# STM32_PCB.net
KiCad netlist of a schematic drawn in Altium Designer
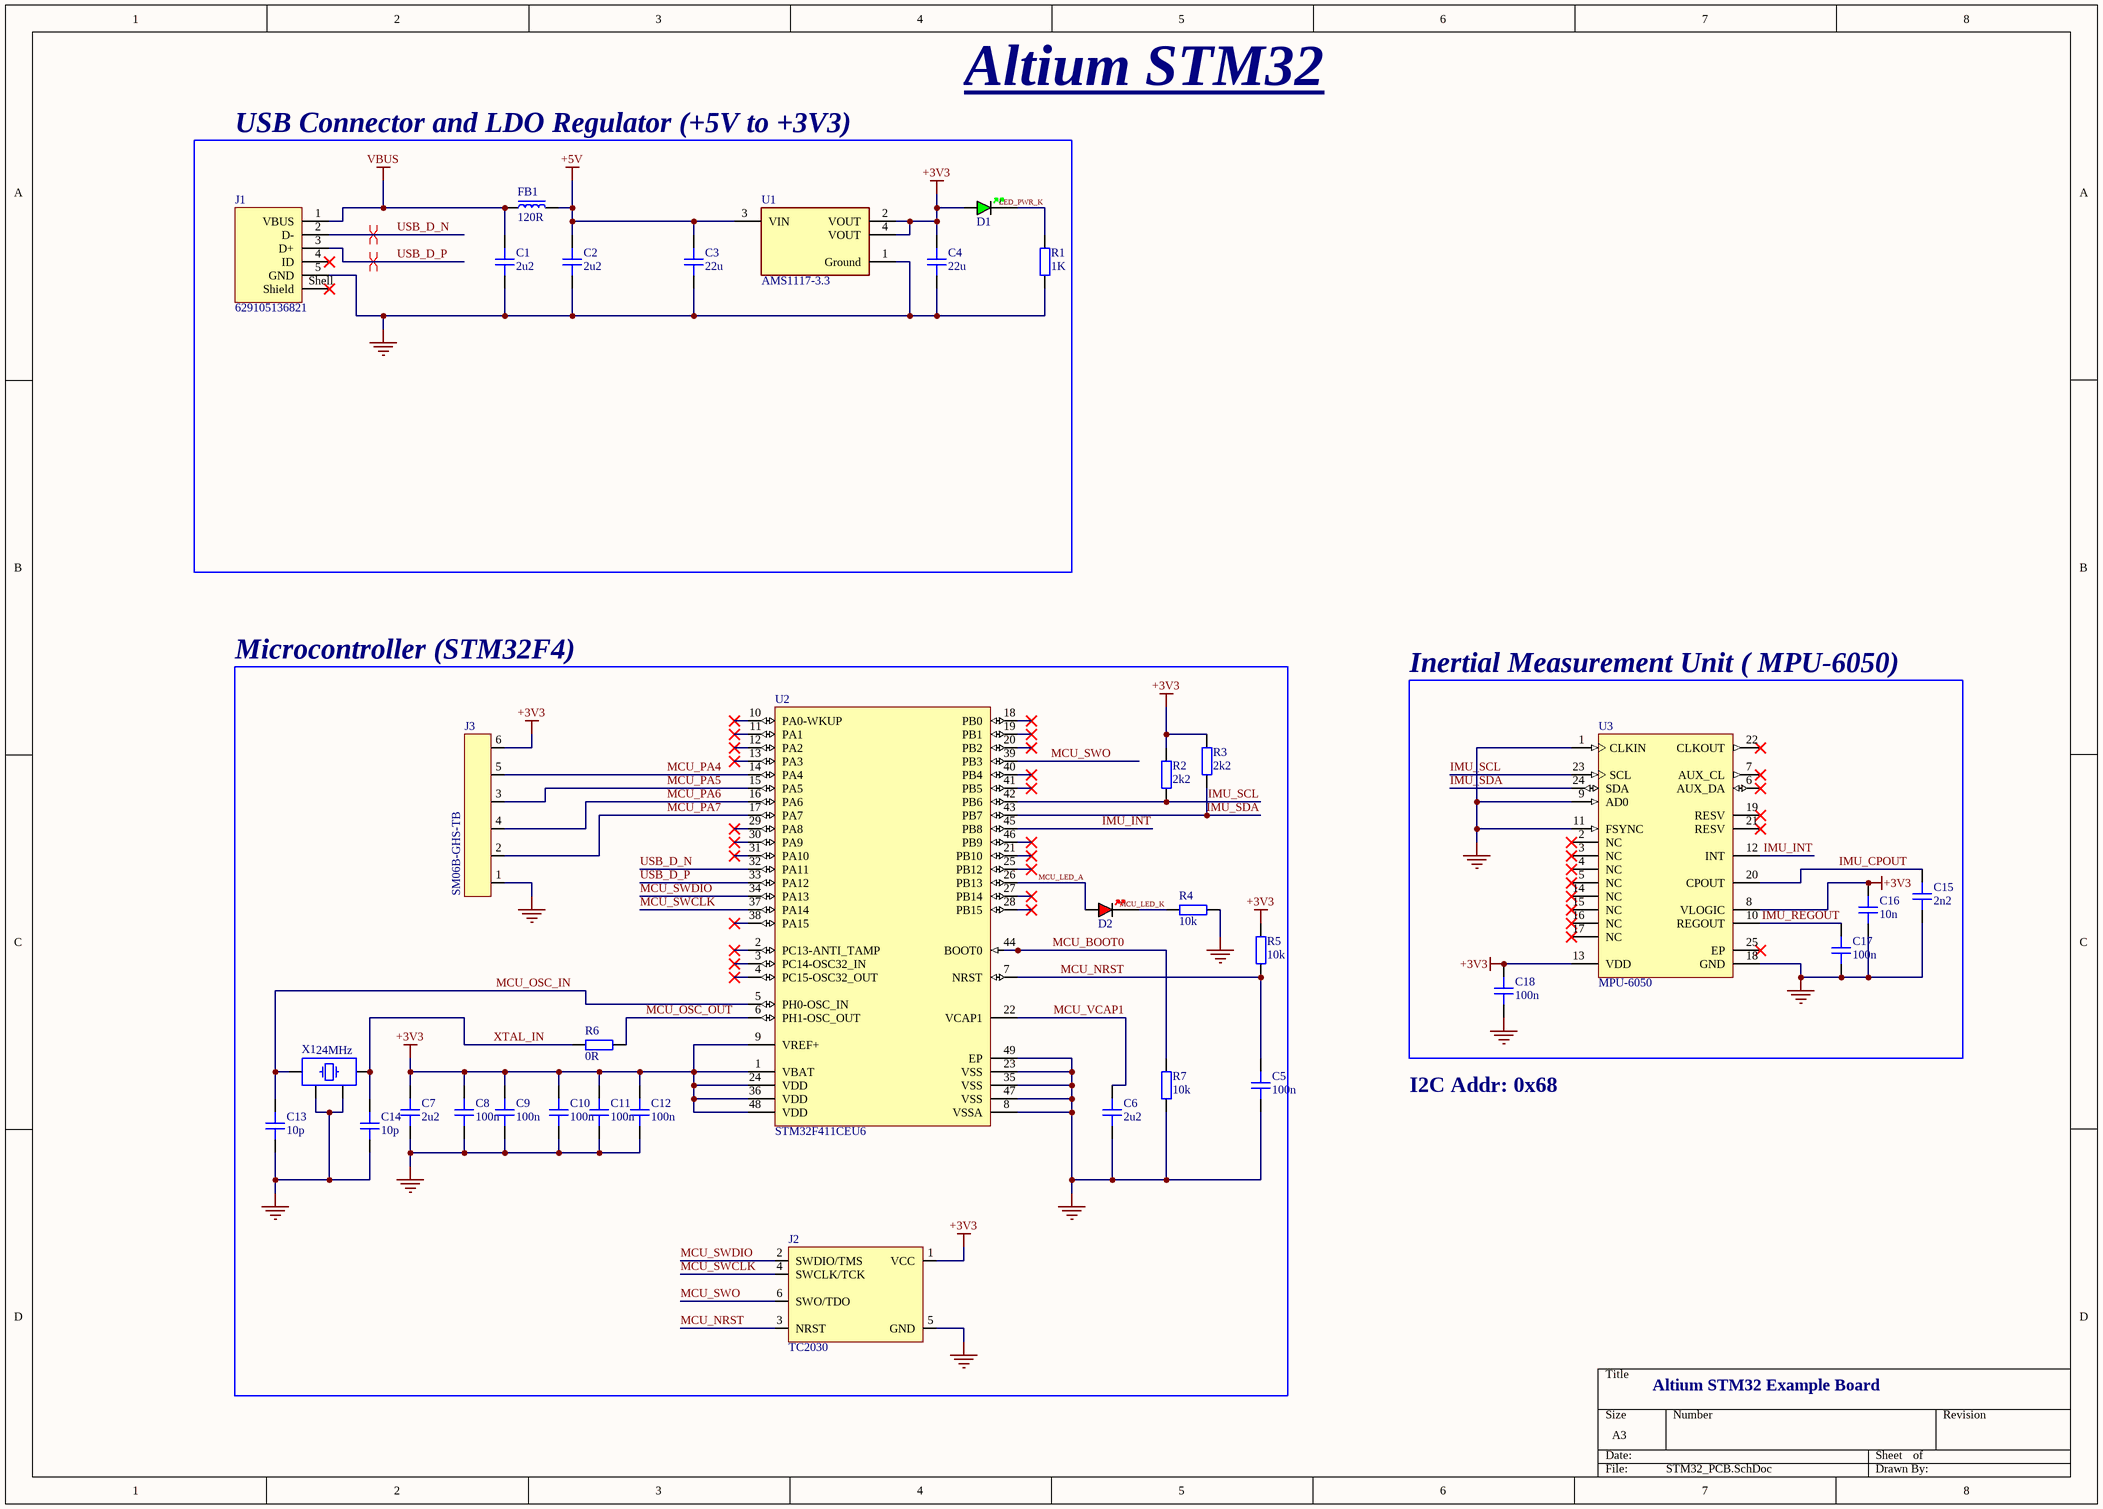
[diagram p0: STM32_PCB.SchDoc]

(export (version "E")
  (design (tool "Eeschema 10.0.6"))
  (components
    (comp (ref "C1")
      (value "2u2")
      (footprint "CAP_0603")
      (description "Capacitor SMD 0603 16V")
      (libsource (lib "Schematic-Lib-PhilsLab") (part "CAP_0603"))
    )
    (comp (ref "C2")
      (value "2u2")
      (footprint "CAP_0603")
      (description "Capacitor SMD 0603 16V")
      (libsource (lib "Schematic-Lib-PhilsLab") (part "CAP_0603"))
    )
    (comp (ref "C3")
      (value "22u")
      (footprint "CAP_0805")
      (description "Capacitor SMD 0805 16V")
      (libsource (lib "Schematic-Lib-PhilsLab") (part "CAP_0805"))
    )
    (comp (ref "C4")
      (value "22u")
      (footprint "CAP_0805")
      (description "Capacitor SMD 0805 16V")
      (libsource (lib "Schematic-Lib-PhilsLab") (part "CAP_0805"))
    )
    (comp (ref "C5")
      (value "100n")
      (footprint "CAP_0402")
      (description "Capacitor SMD 0402 16V")
      (libsource (lib "Schematic-Lib-PhilsLab") (part "CAP_0402"))
    )
    (comp (ref "C6")
      (value "2u2")
      (footprint "CAP_0603")
      (description "Capacitor SMD 0603 16V")
      (libsource (lib "Schematic-Lib-PhilsLab") (part "CAP_0603"))
    )
    (comp (ref "C7")
      (value "2u2")
      (footprint "CAP_0603")
      (description "Capacitor SMD 0603 16V")
      (libsource (lib "Schematic-Lib-PhilsLab") (part "CAP_0603"))
    )
    (comp (ref "C8")
      (value "100n")
      (footprint "CAP_0402")
      (description "Capacitor SMD 0402 16V")
      (libsource (lib "Schematic-Lib-PhilsLab") (part "CAP_0402"))
    )
    (comp (ref "C9")
      (value "100n")
      (footprint "CAP_0402")
      (description "Capacitor SMD 0402 16V")
      (libsource (lib "Schematic-Lib-PhilsLab") (part "CAP_0402"))
    )
    (comp (ref "C10")
      (value "100n")
      (footprint "CAP_0402")
      (description "Capacitor SMD 0402 16V")
      (libsource (lib "Schematic-Lib-PhilsLab") (part "CAP_0402"))
    )
    (comp (ref "C11")
      (value "100n")
      (footprint "CAP_0402")
      (description "Capacitor SMD 0402 16V")
      (libsource (lib "Schematic-Lib-PhilsLab") (part "CAP_0402"))
    )
    (comp (ref "C12")
      (value "100n")
      (footprint "CAP_0402")
      (description "Capacitor SMD 0402 16V")
      (libsource (lib "Schematic-Lib-PhilsLab") (part "CAP_0402"))
    )
    (comp (ref "C13")
      (value "10p")
      (footprint "CAP_0402")
      (description "Capacitor SMD 0402 16V")
      (libsource (lib "Schematic-Lib-PhilsLab") (part "CAP_0402"))
    )
    (comp (ref "C14")
      (value "10p")
      (footprint "CAP_0402")
      (description "Capacitor SMD 0402 16V")
      (libsource (lib "Schematic-Lib-PhilsLab") (part "CAP_0402"))
    )
    (comp (ref "C15")
      (value "2n2")
      (footprint "CAP_0402")
      (description "Capacitor SMD 0402 16V")
      (libsource (lib "Schematic-Lib-PhilsLab") (part "CAP_0402"))
    )
    (comp (ref "C16")
      (value "10n")
      (footprint "CAP_0402")
      (description "Capacitor SMD 0402 16V")
      (libsource (lib "Schematic-Lib-PhilsLab") (part "CAP_0402"))
    )
    (comp (ref "C17")
      (value "100n")
      (footprint "CAP_0402")
      (description "Capacitor SMD 0402 16V")
      (libsource (lib "Schematic-Lib-PhilsLab") (part "CAP_0402"))
    )
    (comp (ref "C18")
      (value "100n")
      (footprint "CAP_0402")
      (description "Capacitor SMD 0402 16V")
      (libsource (lib "Schematic-Lib-PhilsLab") (part "CAP_0402"))
    )
    (comp (ref "D1")
      (value "GREEN")
      (footprint "LED_0402_GREEN")
      (description "LED 0402 GREEN SMD")
      (libsource (lib "Schematic-Lib-PhilsLab") (part "LED_0402_GREEN"))
    )
    (comp (ref "D2")
      (value "RED")
      (footprint "LED_0402_RED")
      (description "LED 0402 RED SMD")
      (libsource (lib "Schematic-Lib-PhilsLab") (part "LED_0402_RED"))
    )
    (comp (ref "FB1")
      (value "120R")
      (footprint "FB_0603")
      (description "Ferrite Bead SMD 0603")
      (libsource (lib "Schematic-Lib-PhilsLab") (part "FB_0603"))
    )
    (comp (ref "J1")
      (value "629105136821")
      (footprint "629105136821")
      (libsource (lib "Altium Content Vault") (part "Micro USB 2.0_Type B_Receptacle_1 Port"))
    )
    (comp (ref "J2")
      (value "TC2030")
      (footprint "TC2030-FP")
      (description "Tag-Connect No-Solder SWD Debug Connector DO NOT PLACE")
      (fields (field (name "MANUFACTURER") "Tag-Connect"))
      (libsource (lib "Schematic-Lib-PhilsLab") (part "TC2030"))
    )
    (comp (ref "J3")
      (value "SM06B-GHS-TB")
      (footprint "SM06B-GHS-TB")
      (description "Header Connector 6 Position 1.25MM Pitch SMD Horizontal JST GH")
      (fields (field (name "MANUFACTURER") "JST"))
      (libsource (lib "Schematic-Lib-PhilsLab") (part "SM06B-GHS-TB"))
    )
    (comp (ref "R1")
      (value "1K")
      (footprint "RES_0402")
      (description "Resistor SMD 0402")
      (libsource (lib "Schematic-Lib-PhilsLab") (part "RES_0402"))
    )
    (comp (ref "R2")
      (value "2k2")
      (footprint "RES_0402")
      (description "Resistor SMD 0402")
      (libsource (lib "Schematic-Lib-PhilsLab") (part "RES_0402"))
    )
    (comp (ref "R3")
      (value "2k2")
      (footprint "RES_0402")
      (description "Resistor SMD 0402")
      (libsource (lib "Schematic-Lib-PhilsLab") (part "RES_0402"))
    )
    (comp (ref "R4")
      (value "10k")
      (footprint "RES_0402")
      (description "Resistor SMD 0402")
      (libsource (lib "Schematic-Lib-PhilsLab") (part "RES_0402"))
    )
    (comp (ref "R5")
      (value "10k")
      (footprint "RES_0402")
      (description "Resistor SMD 0402")
      (libsource (lib "Schematic-Lib-PhilsLab") (part "RES_0402"))
    )
    (comp (ref "R6")
      (value "0R")
      (footprint "RES_0402")
      (description "Resistor SMD 0402")
      (libsource (lib "Schematic-Lib-PhilsLab") (part "RES_0402"))
    )
    (comp (ref "R7")
      (value "10k")
      (footprint "RES_0402")
      (description "Resistor SMD 0402")
      (libsource (lib "Schematic-Lib-PhilsLab") (part "RES_0402"))
    )
    (comp (ref "U1")
      (value "AMS1117-3.3")
      (footprint "FP-AMS1117-IPC_C")
      (description "LDO Voltage Regulators 1A, 3.3V")
      (fields
        (field (name "OCTOPART") "https://octopart.com/ams1117-3.3-advanced+monolithic+systems-25899300")
        (field (name "MANUFACTURER") "Advanced Monolithic Systems")
      )
      (libsource (lib "Altium Content Vault") (part "8bdbb5f8e77002000e30dd2845d0354"))
    )
    (comp (ref "U2")
      (value "STM32F411CEU6")
      (footprint "STM-UFQFPN48_L")
      (libsource (lib "Altium Content Vault") (part "MC-ARM-STM32F411-UFQFPN48"))
    )
    (comp (ref "U3")
      (value "MPU-6050")
      (footprint "IS-QFN-24_V")
      (fields (field (name "MANUFACTURER") "InvenSense"))
      (libsource (lib "Altium Content Vault") (part "IS-MPU-6050-QFN-24"))
    )
    (comp (ref "X1")
      (value "24MHz")
      (footprint "XTAL_3225")
      (description "Crystal SMD 24MHz 10PPM 7pF 3225")
      (fields
        (field (name "MANUFACTURER") "Epson")
        (field (name "MANUFACTURER PART NUMBER") "TSX-3225 24.0000MF15X-AC")
      )
      (libsource (lib "Schematic-Lib-PhilsLab") (part "TSX-3225_24.0000MF15X-AC"))
    )
  )
  (nets
    (net (code "1") (name "+3V3") (class "Default")
      (node (ref "C10") (pin "2") (pinfunction "2_2") (pintype "passive"))
      (node (ref "C11") (pin "2") (pinfunction "2_2") (pintype "passive"))
      (node (ref "C12") (pin "2") (pinfunction "2_2") (pintype "passive"))
      (node (ref "C16") (pin "2") (pinfunction "2_2") (pintype "passive"))
      (node (ref "C18") (pin "2") (pinfunction "2_2") (pintype "passive"))
      (node (ref "C4") (pin "2") (pinfunction "2_2") (pintype "passive"))
      (node (ref "C7") (pin "2") (pinfunction "2_2") (pintype "passive"))
      (node (ref "C8") (pin "2") (pinfunction "2_2") (pintype "passive"))
      (node (ref "C9") (pin "2") (pinfunction "2_2") (pintype "passive"))
      (node (ref "D1") (pin "A") (pinfunction "A_A") (pintype "passive"))
      (node (ref "J2") (pin "1") (pinfunction "VCC_1") (pintype "passive"))
      (node (ref "J3") (pin "6") (pinfunction "6_6") (pintype "passive"))
      (node (ref "R2") (pin "2") (pinfunction "2_2") (pintype "passive"))
      (node (ref "R3") (pin "2") (pinfunction "2_2") (pintype "passive"))
      (node (ref "R5") (pin "2") (pinfunction "2_2") (pintype "passive"))
      (node (ref "U1") (pin "2") (pinfunction "VOUT_2") (pintype "passive"))
      (node (ref "U1") (pin "4") (pinfunction "VOUT_4") (pintype "passive"))
      (node (ref "U2") (pin "1") (pinfunction "VBAT_1") (pintype "power_in"))
      (node (ref "U2") (pin "24") (pinfunction "VDD_24") (pintype "power_in"))
      (node (ref "U2") (pin "36") (pinfunction "VDD_36") (pintype "power_in"))
      (node (ref "U2") (pin "48") (pinfunction "VDD_48") (pintype "power_in"))
      (node (ref "U2") (pin "9") (pinfunction "VREF+_9") (pintype "power_in"))
      (node (ref "U3") (pin "13") (pinfunction "VDD_13") (pintype "power_in"))
      (node (ref "U3") (pin "8") (pinfunction "VLOGIC_8") (pintype "power_in"))
    )
    (net (code "2") (name "+5V") (class "Default")
      (node (ref "C2") (pin "2") (pinfunction "2_2") (pintype "passive"))
      (node (ref "C3") (pin "2") (pinfunction "2_2") (pintype "passive"))
      (node (ref "FB1") (pin "2") (pinfunction "2_2") (pintype "passive"))
      (node (ref "U1") (pin "3") (pinfunction "VIN_3") (pintype "power_in"))
    )
    (net (code "3") (name "/IMU_CPOUT") (class "Default")
      (node (ref "C15") (pin "2") (pinfunction "2_2") (pintype "passive"))
      (node (ref "U3") (pin "20") (pinfunction "CPOUT_20") (pintype "passive"))
    )
    (net (code "4") (name "/IMU_INT") (class "Default")
      (node (ref "U2") (pin "45") (pinfunction "PB8_45") (pintype "bidirectional"))
      (node (ref "U3") (pin "12") (pinfunction "INT_12") (pintype "open_collector"))
    )
    (net (code "5") (name "/IMU_REGOUT") (class "Default")
      (node (ref "C17") (pin "2") (pinfunction "2_2") (pintype "passive"))
      (node (ref "U3") (pin "10") (pinfunction "REGOUT_10") (pintype "passive"))
    )
    (net (code "6") (name "/IMU_SCL") (class "Default")
      (node (ref "R2") (pin "1") (pinfunction "1_1") (pintype "passive"))
      (node (ref "U2") (pin "42") (pinfunction "PB6_42") (pintype "bidirectional"))
      (node (ref "U3") (pin "23") (pinfunction "SCL_23") (pintype "input"))
    )
    (net (code "7") (name "/IMU_SDA") (class "Default")
      (node (ref "R3") (pin "1") (pinfunction "1_1") (pintype "passive"))
      (node (ref "U2") (pin "43") (pinfunction "PB7_43") (pintype "bidirectional"))
      (node (ref "U3") (pin "24") (pinfunction "SDA_24") (pintype "bidirectional"))
    )
    (net (code "8") (name "/LED_PWR_K") (class "Default")
      (node (ref "D1") (pin "K") (pinfunction "K_K") (pintype "passive"))
      (node (ref "R1") (pin "2") (pinfunction "2_2") (pintype "passive"))
    )
    (net (code "9") (name "/MCU_BOOT0") (class "Default")
      (node (ref "R7") (pin "2") (pinfunction "2_2") (pintype "passive"))
      (node (ref "U2") (pin "44") (pinfunction "BOOT0_44") (pintype "input"))
    )
    (net (code "10") (name "/MCU_LED_A") (class "Default")
      (node (ref "D2") (pin "A") (pinfunction "A_A") (pintype "passive"))
      (node (ref "U2") (pin "26") (pinfunction "PB13_26") (pintype "bidirectional"))
    )
    (net (code "11") (name "/MCU_LED_K") (class "Default")
      (node (ref "D2") (pin "K") (pinfunction "K_K") (pintype "passive"))
      (node (ref "R4") (pin "2") (pinfunction "2_2") (pintype "passive"))
    )
    (net (code "12") (name "/MCU_NRST") (class "Default")
      (node (ref "C5") (pin "2") (pinfunction "2_2") (pintype "passive"))
      (node (ref "J2") (pin "3") (pinfunction "NRST_3") (pintype "passive"))
      (node (ref "R5") (pin "1") (pinfunction "1_1") (pintype "passive"))
      (node (ref "U2") (pin "7") (pinfunction "NRST_7") (pintype "bidirectional"))
    )
    (net (code "13") (name "/MCU_OSC_IN") (class "Default")
      (node (ref "C13") (pin "2") (pinfunction "2_2") (pintype "passive"))
      (node (ref "U2") (pin "5") (pinfunction "PH0-OSC_IN_5") (pintype "bidirectional"))
      (node (ref "X1") (pin "1") (pinfunction "1_1") (pintype "passive"))
    )
    (net (code "14") (name "/MCU_OSC_OUT") (class "Default")
      (node (ref "R6") (pin "1") (pinfunction "1_1") (pintype "passive"))
      (node (ref "U2") (pin "6") (pinfunction "PH1-OSC_OUT_6") (pintype "bidirectional"))
    )
    (net (code "15") (name "/MCU_PA4") (class "Default")
      (node (ref "J3") (pin "5") (pinfunction "5_5") (pintype "passive"))
      (node (ref "U2") (pin "14") (pinfunction "PA4_14") (pintype "bidirectional"))
    )
    (net (code "16") (name "/MCU_PA5") (class "Default")
      (node (ref "J3") (pin "3") (pinfunction "3_3") (pintype "passive"))
      (node (ref "U2") (pin "15") (pinfunction "PA5_15") (pintype "bidirectional"))
    )
    (net (code "17") (name "/MCU_PA6") (class "Default")
      (node (ref "J3") (pin "4") (pinfunction "4_4") (pintype "passive"))
      (node (ref "U2") (pin "16") (pinfunction "PA6_16") (pintype "bidirectional"))
    )
    (net (code "18") (name "/MCU_PA7") (class "Default")
      (node (ref "J3") (pin "2") (pinfunction "2_2") (pintype "passive"))
      (node (ref "U2") (pin "17") (pinfunction "PA7_17") (pintype "bidirectional"))
    )
    (net (code "19") (name "/MCU_SWCLK") (class "Default")
      (node (ref "J2") (pin "4") (pinfunction "SWCLK/TCK_4") (pintype "passive"))
      (node (ref "U2") (pin "37") (pinfunction "PA14_37") (pintype "bidirectional"))
    )
    (net (code "20") (name "/MCU_SWDIO") (class "Default")
      (node (ref "J2") (pin "2") (pinfunction "SWDIO/TMS_2") (pintype "passive"))
      (node (ref "U2") (pin "34") (pinfunction "PA13_34") (pintype "bidirectional"))
    )
    (net (code "21") (name "/MCU_SWO") (class "Default")
      (node (ref "J2") (pin "6") (pinfunction "SWO/TDO_6") (pintype "passive"))
      (node (ref "U2") (pin "39") (pinfunction "PB3_39") (pintype "bidirectional"))
    )
    (net (code "22") (name "/MCU_VCAP1") (class "Default")
      (node (ref "C6") (pin "2") (pinfunction "2_2") (pintype "passive"))
      (node (ref "U2") (pin "22") (pinfunction "VCAP1_22") (pintype "passive"))
    )
    (net (code "23") (name "/USB_D_N") (class "Default")
      (node (ref "J1") (pin "2") (pinfunction "D-_2") (pintype "passive"))
      (node (ref "U2") (pin "32") (pinfunction "PA11_32") (pintype "bidirectional"))
    )
    (net (code "24") (name "/USB_D_P") (class "Default")
      (node (ref "J1") (pin "3") (pinfunction "D+_3") (pintype "passive"))
      (node (ref "U2") (pin "33") (pinfunction "PA12_33") (pintype "bidirectional"))
    )
    (net (code "25") (name "/XTAL_IN") (class "Default")
      (node (ref "C14") (pin "2") (pinfunction "2_2") (pintype "passive"))
      (node (ref "R6") (pin "2") (pinfunction "2_2") (pintype "passive"))
      (node (ref "X1") (pin "3") (pinfunction "3_3") (pintype "passive"))
    )
    (net (code "26") (name "GND") (class "Default")
      (node (ref "C1") (pin "1") (pinfunction "1_1") (pintype "passive"))
      (node (ref "C10") (pin "1") (pinfunction "1_1") (pintype "passive"))
      (node (ref "C11") (pin "1") (pinfunction "1_1") (pintype "passive"))
      (node (ref "C12") (pin "1") (pinfunction "1_1") (pintype "passive"))
      (node (ref "C13") (pin "1") (pinfunction "1_1") (pintype "passive"))
      (node (ref "C14") (pin "1") (pinfunction "1_1") (pintype "passive"))
      (node (ref "C15") (pin "1") (pinfunction "1_1") (pintype "passive"))
      (node (ref "C16") (pin "1") (pinfunction "1_1") (pintype "passive"))
      (node (ref "C17") (pin "1") (pinfunction "1_1") (pintype "passive"))
      (node (ref "C18") (pin "1") (pinfunction "1_1") (pintype "passive"))
      (node (ref "C2") (pin "1") (pinfunction "1_1") (pintype "passive"))
      (node (ref "C3") (pin "1") (pinfunction "1_1") (pintype "passive"))
      (node (ref "C4") (pin "1") (pinfunction "1_1") (pintype "passive"))
      (node (ref "C5") (pin "1") (pinfunction "1_1") (pintype "passive"))
      (node (ref "C6") (pin "1") (pinfunction "1_1") (pintype "passive"))
      (node (ref "C7") (pin "1") (pinfunction "1_1") (pintype "passive"))
      (node (ref "C8") (pin "1") (pinfunction "1_1") (pintype "passive"))
      (node (ref "C9") (pin "1") (pinfunction "1_1") (pintype "passive"))
      (node (ref "J1") (pin "5") (pinfunction "GND_5") (pintype "passive"))
      (node (ref "J2") (pin "5") (pinfunction "GND_5") (pintype "passive"))
      (node (ref "J3") (pin "1") (pinfunction "1_1") (pintype "passive"))
      (node (ref "R1") (pin "1") (pinfunction "1_1") (pintype "passive"))
      (node (ref "R4") (pin "1") (pinfunction "1_1") (pintype "passive"))
      (node (ref "R7") (pin "1") (pinfunction "1_1") (pintype "passive"))
      (node (ref "U1") (pin "1") (pinfunction "Ground_1") (pintype "power_in"))
      (node (ref "U2") (pin "23") (pinfunction "VSS_23") (pintype "power_in"))
      (node (ref "U2") (pin "35") (pinfunction "VSS_35") (pintype "power_in"))
      (node (ref "U2") (pin "47") (pinfunction "VSS_47") (pintype "power_in"))
      (node (ref "U2") (pin "49") (pinfunction "EP_49") (pintype "power_in"))
      (node (ref "U2") (pin "8") (pinfunction "VSSA_8") (pintype "power_in"))
      (node (ref "U3") (pin "1") (pinfunction "CLKIN_1") (pintype "input"))
      (node (ref "U3") (pin "11") (pinfunction "FSYNC_11") (pintype "input"))
      (node (ref "U3") (pin "18") (pinfunction "GND_18") (pintype "power_in"))
      (node (ref "U3") (pin "9") (pinfunction "AD0_9") (pintype "input"))
      (node (ref "X1") (pin "2") (pinfunction "2_2") (pintype "passive"))
      (node (ref "X1") (pin "4") (pinfunction "4_4") (pintype "passive"))
    )
    (net (code "27") (name "VBUS") (class "Default")
      (node (ref "C1") (pin "2") (pinfunction "2_2") (pintype "passive"))
      (node (ref "FB1") (pin "1") (pinfunction "1_1") (pintype "passive"))
      (node (ref "J1") (pin "1") (pinfunction "VBUS_1") (pintype "passive"))
    )
    (net (code "28") (name "unconnected-(J1-ID-Pad4)") (class "Default")
      (node (ref "J1") (pin "4") (pinfunction "ID_4") (pintype "passive+no_connect"))
    )
    (net (code "29") (name "unconnected-(J1-Shield-PadShell)") (class "Default")
      (node (ref "J1") (pin "Shell") (pinfunction "Shield_Shell") (pintype "passive+no_connect"))
    )
    (net (code "30") (name "unconnected-(U2-PA0-WKUP-Pad10)") (class "Default")
      (node (ref "U2") (pin "10") (pinfunction "PA0-WKUP_10") (pintype "bidirectional+no_connect"))
    )
    (net (code "31") (name "unconnected-(U2-PA1-Pad11)") (class "Default")
      (node (ref "U2") (pin "11") (pinfunction "PA1_11") (pintype "bidirectional+no_connect"))
    )
    (net (code "32") (name "unconnected-(U2-PA2-Pad12)") (class "Default")
      (node (ref "U2") (pin "12") (pinfunction "PA2_12") (pintype "bidirectional+no_connect"))
    )
    (net (code "33") (name "unconnected-(U2-PA3-Pad13)") (class "Default")
      (node (ref "U2") (pin "13") (pinfunction "PA3_13") (pintype "bidirectional+no_connect"))
    )
    (net (code "34") (name "unconnected-(U2-PA8-Pad29)") (class "Default")
      (node (ref "U2") (pin "29") (pinfunction "PA8_29") (pintype "bidirectional+no_connect"))
    )
    (net (code "35") (name "unconnected-(U2-PA9-Pad30)") (class "Default")
      (node (ref "U2") (pin "30") (pinfunction "PA9_30") (pintype "bidirectional+no_connect"))
    )
    (net (code "36") (name "unconnected-(U2-PA10-Pad31)") (class "Default")
      (node (ref "U2") (pin "31") (pinfunction "PA10_31") (pintype "bidirectional+no_connect"))
    )
    (net (code "37") (name "unconnected-(U2-PA15-Pad38)") (class "Default")
      (node (ref "U2") (pin "38") (pinfunction "PA15_38") (pintype "bidirectional+no_connect"))
    )
    (net (code "38") (name "unconnected-(U2-PB0-Pad18)") (class "Default")
      (node (ref "U2") (pin "18") (pinfunction "PB0_18") (pintype "bidirectional+no_connect"))
    )
    (net (code "39") (name "unconnected-(U2-PB1-Pad19)") (class "Default")
      (node (ref "U2") (pin "19") (pinfunction "PB1_19") (pintype "bidirectional+no_connect"))
    )
    (net (code "40") (name "unconnected-(U2-PB2-Pad20)") (class "Default")
      (node (ref "U2") (pin "20") (pinfunction "PB2_20") (pintype "bidirectional+no_connect"))
    )
    (net (code "41") (name "unconnected-(U2-PB4-Pad40)") (class "Default")
      (node (ref "U2") (pin "40") (pinfunction "PB4_40") (pintype "bidirectional+no_connect"))
    )
    (net (code "42") (name "unconnected-(U2-PB5-Pad41)") (class "Default")
      (node (ref "U2") (pin "41") (pinfunction "PB5_41") (pintype "bidirectional+no_connect"))
    )
    (net (code "43") (name "unconnected-(U2-PB9-Pad46)") (class "Default")
      (node (ref "U2") (pin "46") (pinfunction "PB9_46") (pintype "bidirectional+no_connect"))
    )
    (net (code "44") (name "unconnected-(U2-PB10-Pad21)") (class "Default")
      (node (ref "U2") (pin "21") (pinfunction "PB10_21") (pintype "bidirectional+no_connect"))
    )
    (net (code "45") (name "unconnected-(U2-PB12-Pad25)") (class "Default")
      (node (ref "U2") (pin "25") (pinfunction "PB12_25") (pintype "bidirectional+no_connect"))
    )
    (net (code "46") (name "unconnected-(U2-PB14-Pad27)") (class "Default")
      (node (ref "U2") (pin "27") (pinfunction "PB14_27") (pintype "bidirectional+no_connect"))
    )
    (net (code "47") (name "unconnected-(U2-PB15-Pad28)") (class "Default")
      (node (ref "U2") (pin "28") (pinfunction "PB15_28") (pintype "bidirectional+no_connect"))
    )
    (net (code "48") (name "unconnected-(U2-PC13-ANTI_TAMP-Pad2)") (class "Default")
      (node (ref "U2") (pin "2") (pinfunction "PC13-ANTI_TAMP_2") (pintype "bidirectional+no_connect"))
    )
    (net (code "49") (name "unconnected-(U2-PC14-OSC32_IN-Pad3)") (class "Default")
      (node (ref "U2") (pin "3") (pinfunction "PC14-OSC32_IN_3") (pintype "bidirectional+no_connect"))
    )
    (net (code "50") (name "unconnected-(U2-PC15-OSC32_OUT-Pad4)") (class "Default")
      (node (ref "U2") (pin "4") (pinfunction "PC15-OSC32_OUT_4") (pintype "bidirectional+no_connect"))
    )
    (net (code "51") (name "unconnected-(U3-AUX_CL-Pad7)") (class "Default")
      (node (ref "U3") (pin "7") (pinfunction "AUX_CL_7") (pintype "output+no_connect"))
    )
    (net (code "52") (name "unconnected-(U3-AUX_DA-Pad6)") (class "Default")
      (node (ref "U3") (pin "6") (pinfunction "AUX_DA_6") (pintype "bidirectional+no_connect"))
    )
    (net (code "53") (name "unconnected-(U3-CLKOUT-Pad22)") (class "Default")
      (node (ref "U3") (pin "22") (pinfunction "CLKOUT_22") (pintype "output+no_connect"))
    )
    (net (code "54") (name "unconnected-(U3-EP-Pad25)") (class "Default")
      (node (ref "U3") (pin "25") (pinfunction "EP_25") (pintype "power_in+no_connect"))
    )
    (net (code "55") (name "unconnected-(U3-NC-Pad2)") (class "Default")
      (node (ref "U3") (pin "2") (pinfunction "NC_2") (pintype "passive+no_connect"))
    )
    (net (code "56") (name "unconnected-(U3-NC-Pad3)") (class "Default")
      (node (ref "U3") (pin "3") (pinfunction "NC_3") (pintype "passive+no_connect"))
    )
    (net (code "57") (name "unconnected-(U3-NC-Pad4)") (class "Default")
      (node (ref "U3") (pin "4") (pinfunction "NC_4") (pintype "passive+no_connect"))
    )
    (net (code "58") (name "unconnected-(U3-NC-Pad5)") (class "Default")
      (node (ref "U3") (pin "5") (pinfunction "NC_5") (pintype "passive+no_connect"))
    )
    (net (code "59") (name "unconnected-(U3-NC-Pad14)") (class "Default")
      (node (ref "U3") (pin "14") (pinfunction "NC_14") (pintype "passive+no_connect"))
    )
    (net (code "60") (name "unconnected-(U3-NC-Pad15)") (class "Default")
      (node (ref "U3") (pin "15") (pinfunction "NC_15") (pintype "passive+no_connect"))
    )
    (net (code "61") (name "unconnected-(U3-NC-Pad16)") (class "Default")
      (node (ref "U3") (pin "16") (pinfunction "NC_16") (pintype "passive+no_connect"))
    )
    (net (code "62") (name "unconnected-(U3-NC-Pad17)") (class "Default")
      (node (ref "U3") (pin "17") (pinfunction "NC_17") (pintype "passive+no_connect"))
    )
    (net (code "63") (name "unconnected-(U3-RESV-Pad19)") (class "Default")
      (node (ref "U3") (pin "19") (pinfunction "RESV_19") (pintype "passive+no_connect"))
    )
    (net (code "64") (name "unconnected-(U3-RESV-Pad21)") (class "Default")
      (node (ref "U3") (pin "21") (pinfunction "RESV_21") (pintype "passive+no_connect"))
    )
  )
)
